# Drive.net
KiCad netlist of a schematic drawn in Altium Designer
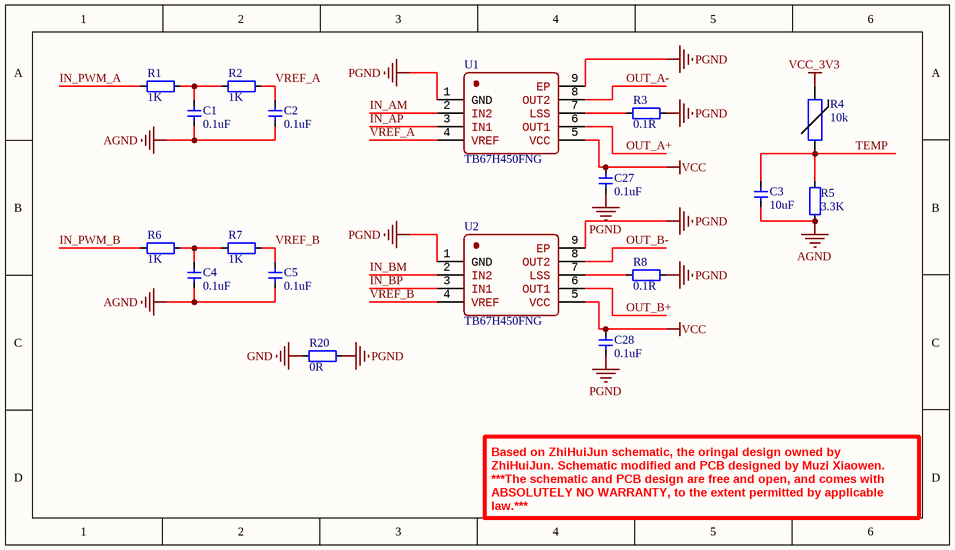
[diagram p0: Drive.SchDoc]

(export (version "E")
  (design (tool "Eeschema 10.0.6"))
  (components
    (comp (ref "C1")
      (value "0.1uF")
      (footprint "motor42-lib:CAP_0402")
      (description "Capacitor")
      (libsource (lib "MyPcbLib") (part "电容-0402"))
    )
    (comp (ref "C2")
      (value "0.1uF")
      (footprint "motor42-lib:CAP_0402")
      (description "Capacitor")
      (libsource (lib "MyPcbLib") (part "电容-0402"))
    )
    (comp (ref "C3")
      (value "10uF")
      (footprint "CAP_0402")
      (description "Capacitor")
      (libsource (lib "MyPcbLib") (part "电容-0402"))
    )
    (comp (ref "C4")
      (value "0.1uF")
      (footprint "motor42-lib:CAP_0402")
      (description "Capacitor")
      (libsource (lib "MyPcbLib") (part "电容-0402"))
    )
    (comp (ref "C5")
      (value "0.1uF")
      (footprint "motor42-lib:CAP_0402")
      (description "Capacitor")
      (libsource (lib "MyPcbLib") (part "电容-0402"))
    )
    (comp (ref "C27")
      (value "0.1uF")
      (footprint "CAP_0402")
      (description "Capacitor")
      (libsource (lib "MyPcbLib") (part "电容-0402"))
    )
    (comp (ref "C28")
      (value "0.1uF")
      (footprint "motor42-lib:CAP_0402")
      (description "Capacitor")
      (libsource (lib "MyPcbLib") (part "电容-0402"))
    )
    (comp (ref "R1")
      (value "1K")
      (footprint "RES_0402")
      (description "Resistor")
      (libsource (lib "") (part "电阻-0402_1"))
    )
    (comp (ref "R2")
      (value "1K")
      (footprint "RES_0402")
      (description "Resistor")
      (libsource (lib "") (part "电阻-0402_1"))
    )
    (comp (ref "R3")
      (value "0.1R")
      (footprint "1206-RES")
      (description "Resistor")
      (libsource (lib "MyPcbLib") (part "电阻-1206"))
    )
    (comp (ref "R4")
      (value "10k")
      (footprint "RES_0402")
      (description "THERMISTOR 10K OHM NTC 0402 SMD")
      (fields (field (name "Comment") "NCP15XH103F03RC"))
      (libsource (lib "MyPcbLib") (part "NCP15XH103F03RC"))
    )
    (comp (ref "R5")
      (value "3.3K")
      (footprint "RES_0402")
      (description "Resistor")
      (libsource (lib "MyPcbLib") (part "电阻-0402"))
    )
    (comp (ref "R6")
      (value "1K")
      (footprint "RES_0402")
      (description "Resistor")
      (libsource (lib "") (part "电阻-0402_1"))
    )
    (comp (ref "R7")
      (value "1K")
      (footprint "RES_0402")
      (description "Resistor")
      (libsource (lib "") (part "电阻-0402_1"))
    )
    (comp (ref "R8")
      (value "0.1R")
      (footprint "1206-RES")
      (description "Resistor")
      (libsource (lib "MyPcbLib") (part "电阻-1206"))
    )
    (comp (ref "R20")
      (value "0R")
      (footprint "1206-RES")
      (description "Resistor")
      (libsource (lib "MyPcbLib") (part "电阻-1206"))
    )
    (comp (ref "U1")
      (value "TB67H450FNG")
      (footprint "SO-8-PAD")
      (description "PWM Chopper Type DC Brushed Motor Driver")
      (libsource (lib "MyPcbLib") (part "TB67H450FNG"))
    )
    (comp (ref "U2")
      (value "TB67H450FNG")
      (footprint "SO-8-PAD")
      (description "PWM Chopper Type DC Brushed Motor Driver")
      (libsource (lib "MyPcbLib") (part "TB67H450FNG"))
    )
  )
  (nets
    (net (code "1") (name "/IN_AM") (class "Default")
      (node (ref "U1") (pin "2") (pinfunction "IN2_2") (pintype "passive"))
    )
    (net (code "2") (name "/IN_AP") (class "Default")
      (node (ref "U1") (pin "3") (pinfunction "IN1_3") (pintype "passive"))
    )
    (net (code "3") (name "/IN_BM") (class "Default")
      (node (ref "U2") (pin "2") (pinfunction "IN2_2") (pintype "passive"))
    )
    (net (code "4") (name "/IN_BP") (class "Default")
      (node (ref "U2") (pin "3") (pinfunction "IN1_3") (pintype "passive"))
    )
    (net (code "5") (name "/IN_PWM_A") (class "Default")
      (node (ref "R1") (pin "1") (pinfunction "1_1") (pintype "passive"))
    )
    (net (code "6") (name "/IN_PWM_B") (class "Default")
      (node (ref "R6") (pin "1") (pinfunction "1_1") (pintype "passive"))
    )
    (net (code "7") (name "/OUT_A+") (class "Default")
      (node (ref "U1") (pin "6") (pinfunction "OUT1_6") (pintype "passive"))
    )
    (net (code "8") (name "/OUT_A-") (class "Default")
      (node (ref "U1") (pin "8") (pinfunction "OUT2_8") (pintype "passive"))
    )
    (net (code "9") (name "/OUT_B+") (class "Default")
      (node (ref "U2") (pin "6") (pinfunction "OUT1_6") (pintype "passive"))
    )
    (net (code "10") (name "/OUT_B-") (class "Default")
      (node (ref "U2") (pin "8") (pinfunction "OUT2_8") (pintype "passive"))
    )
    (net (code "11") (name "/TEMP") (class "Default")
      (node (ref "C3") (pin "2") (pinfunction "2_2") (pintype "passive"))
      (node (ref "R4") (pin "1") (pinfunction "0_1") (pintype "passive"))
      (node (ref "R5") (pin "2") (pinfunction "2_2") (pintype "passive"))
    )
    (net (code "12") (name "/VREF_A") (class "Default")
      (node (ref "C2") (pin "2") (pinfunction "2_2") (pintype "passive"))
      (node (ref "R2") (pin "2") (pinfunction "2_2") (pintype "passive"))
      (node (ref "U1") (pin "4") (pinfunction "VREF_4") (pintype "passive"))
    )
    (net (code "13") (name "/VREF_B") (class "Default")
      (node (ref "C5") (pin "2") (pinfunction "2_2") (pintype "passive"))
      (node (ref "R7") (pin "2") (pinfunction "2_2") (pintype "passive"))
      (node (ref "U2") (pin "4") (pinfunction "VREF_4") (pintype "passive"))
    )
    (net (code "14") (name "AGND") (class "Default")
      (node (ref "C1") (pin "1") (pinfunction "1_1") (pintype "passive"))
      (node (ref "C2") (pin "1") (pinfunction "1_1") (pintype "passive"))
      (node (ref "C3") (pin "1") (pinfunction "1_1") (pintype "passive"))
      (node (ref "C4") (pin "1") (pinfunction "1_1") (pintype "passive"))
      (node (ref "C5") (pin "1") (pinfunction "1_1") (pintype "passive"))
      (node (ref "R5") (pin "1") (pinfunction "1_1") (pintype "passive"))
    )
    (net (code "15") (name "GND") (class "Default")
      (node (ref "R20") (pin "1") (pinfunction "1_1") (pintype "passive"))
    )
    (net (code "16") (name "Net-(C1-Pad2)") (class "Default")
      (node (ref "C1") (pin "2") (pinfunction "2_2") (pintype "passive"))
      (node (ref "R1") (pin "2") (pinfunction "2_2") (pintype "passive"))
      (node (ref "R2") (pin "1") (pinfunction "1_1") (pintype "passive"))
    )
    (net (code "17") (name "Net-(C4-Pad2)") (class "Default")
      (node (ref "C4") (pin "2") (pinfunction "2_2") (pintype "passive"))
      (node (ref "R6") (pin "2") (pinfunction "2_2") (pintype "passive"))
      (node (ref "R7") (pin "1") (pinfunction "1_1") (pintype "passive"))
    )
    (net (code "18") (name "Net-(U1-LSS)") (class "Default")
      (node (ref "R3") (pin "1") (pinfunction "1_1") (pintype "passive"))
      (node (ref "U1") (pin "7") (pinfunction "LSS_7") (pintype "passive"))
    )
    (net (code "19") (name "Net-(U2-LSS)") (class "Default")
      (node (ref "R8") (pin "1") (pinfunction "1_1") (pintype "passive"))
      (node (ref "U2") (pin "7") (pinfunction "LSS_7") (pintype "passive"))
    )
    (net (code "20") (name "PGND") (class "Default")
      (node (ref "C27") (pin "1") (pinfunction "1_1") (pintype "passive"))
      (node (ref "C28") (pin "1") (pinfunction "1_1") (pintype "passive"))
      (node (ref "R20") (pin "2") (pinfunction "2_2") (pintype "passive"))
      (node (ref "R3") (pin "2") (pinfunction "2_2") (pintype "passive"))
      (node (ref "R8") (pin "2") (pinfunction "2_2") (pintype "passive"))
      (node (ref "U1") (pin "1") (pinfunction "GND_1") (pintype "passive"))
      (node (ref "U1") (pin "9") (pinfunction "EP_9") (pintype "passive"))
      (node (ref "U2") (pin "1") (pinfunction "GND_1") (pintype "passive"))
      (node (ref "U2") (pin "9") (pinfunction "EP_9") (pintype "passive"))
    )
    (net (code "21") (name "VCC") (class "Default")
      (node (ref "C27") (pin "2") (pinfunction "2_2") (pintype "passive"))
      (node (ref "C28") (pin "2") (pinfunction "2_2") (pintype "passive"))
      (node (ref "U1") (pin "5") (pinfunction "VCC_5") (pintype "passive"))
      (node (ref "U2") (pin "5") (pinfunction "VCC_5") (pintype "passive"))
    )
    (net (code "22") (name "VCC_3V3") (class "Default")
      (node (ref "R4") (pin "2") (pinfunction "0_2") (pintype "passive"))
    )
  )
)
